# LEDBreakOutBoard.net
KiCad netlist of a schematic drawn in EAGLE
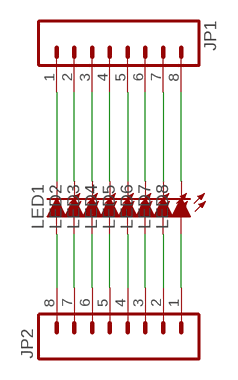
[diagram p0: schematic, sheet 1]

(export (version "E")
  (design (tool "Eeschema 10.0.6"))
  (components
    (comp (ref "JP1")
      (value "M08")
      (footprint "eagle-import:1X08")
      (libsource (lib "eagle-import") (part "M08"))
    )
    (comp (ref "JP2")
      (value "M08")
      (footprint "eagle-import:1X08")
      (libsource (lib "eagle-import") (part "M08"))
    )
    (comp (ref "LED1")
      (value "LED-0805")
      (footprint "eagle-import:LED-805")
      (libsource (lib "eagle-import") (part "LED-0805"))
    )
    (comp (ref "LED2")
      (value "LED-0805")
      (footprint "eagle-import:LED-805")
      (libsource (lib "eagle-import") (part "LED-0805"))
    )
    (comp (ref "LED3")
      (value "LED-0805")
      (footprint "eagle-import:LED-805")
      (libsource (lib "eagle-import") (part "LED-0805"))
    )
    (comp (ref "LED4")
      (value "LED-0805")
      (footprint "eagle-import:LED-805")
      (libsource (lib "eagle-import") (part "LED-0805"))
    )
    (comp (ref "LED5")
      (value "LED-0805")
      (footprint "eagle-import:LED-805")
      (libsource (lib "eagle-import") (part "LED-0805"))
    )
    (comp (ref "LED6")
      (value "LED-0805")
      (footprint "eagle-import:LED-805")
      (libsource (lib "eagle-import") (part "LED-0805"))
    )
    (comp (ref "LED7")
      (value "LED-0805")
      (footprint "eagle-import:LED-805")
      (libsource (lib "eagle-import") (part "LED-0805"))
    )
    (comp (ref "LED8")
      (value "LED-0805")
      (footprint "eagle-import:LED-805")
      (libsource (lib "eagle-import") (part "LED-0805"))
    )
  )
  (nets
    (net (code "1") (name "Net-(JP1-Pad1)") (class "Default")
      (node (ref "JP1") (pin "1") (pinfunction "1_1") (pintype "passive"))
      (node (ref "LED1") (pin "C") (pinfunction "C_C") (pintype "passive"))
    )
    (net (code "2") (name "Net-(JP1-Pad2)") (class "Default")
      (node (ref "JP1") (pin "2") (pinfunction "2_2") (pintype "passive"))
      (node (ref "LED2") (pin "C") (pinfunction "C_C") (pintype "passive"))
    )
    (net (code "3") (name "Net-(JP1-Pad3)") (class "Default")
      (node (ref "JP1") (pin "3") (pinfunction "3_3") (pintype "passive"))
      (node (ref "LED3") (pin "C") (pinfunction "C_C") (pintype "passive"))
    )
    (net (code "4") (name "Net-(JP1-Pad4)") (class "Default")
      (node (ref "JP1") (pin "4") (pinfunction "4_4") (pintype "passive"))
      (node (ref "LED4") (pin "C") (pinfunction "C_C") (pintype "passive"))
    )
    (net (code "5") (name "Net-(JP1-Pad5)") (class "Default")
      (node (ref "JP1") (pin "5") (pinfunction "5_5") (pintype "passive"))
      (node (ref "LED5") (pin "C") (pinfunction "C_C") (pintype "passive"))
    )
    (net (code "6") (name "Net-(JP1-Pad6)") (class "Default")
      (node (ref "JP1") (pin "6") (pinfunction "6_6") (pintype "passive"))
      (node (ref "LED6") (pin "C") (pinfunction "C_C") (pintype "passive"))
    )
    (net (code "7") (name "Net-(JP1-Pad7)") (class "Default")
      (node (ref "JP1") (pin "7") (pinfunction "7_7") (pintype "passive"))
      (node (ref "LED7") (pin "C") (pinfunction "C_C") (pintype "passive"))
    )
    (net (code "8") (name "Net-(JP1-Pad8)") (class "Default")
      (node (ref "JP1") (pin "8") (pinfunction "8_8") (pintype "passive"))
      (node (ref "LED8") (pin "C") (pinfunction "C_C") (pintype "passive"))
    )
    (net (code "9") (name "Net-(JP2-Pad1)") (class "Default")
      (node (ref "JP2") (pin "1") (pinfunction "1_1") (pintype "passive"))
      (node (ref "LED8") (pin "A") (pinfunction "A_A") (pintype "passive"))
    )
    (net (code "10") (name "Net-(JP2-Pad2)") (class "Default")
      (node (ref "JP2") (pin "2") (pinfunction "2_2") (pintype "passive"))
      (node (ref "LED7") (pin "A") (pinfunction "A_A") (pintype "passive"))
    )
    (net (code "11") (name "Net-(JP2-Pad3)") (class "Default")
      (node (ref "JP2") (pin "3") (pinfunction "3_3") (pintype "passive"))
      (node (ref "LED6") (pin "A") (pinfunction "A_A") (pintype "passive"))
    )
    (net (code "12") (name "Net-(JP2-Pad4)") (class "Default")
      (node (ref "JP2") (pin "4") (pinfunction "4_4") (pintype "passive"))
      (node (ref "LED5") (pin "A") (pinfunction "A_A") (pintype "passive"))
    )
    (net (code "13") (name "Net-(JP2-Pad5)") (class "Default")
      (node (ref "JP2") (pin "5") (pinfunction "5_5") (pintype "passive"))
      (node (ref "LED4") (pin "A") (pinfunction "A_A") (pintype "passive"))
    )
    (net (code "14") (name "Net-(JP2-Pad6)") (class "Default")
      (node (ref "JP2") (pin "6") (pinfunction "6_6") (pintype "passive"))
      (node (ref "LED3") (pin "A") (pinfunction "A_A") (pintype "passive"))
    )
    (net (code "15") (name "Net-(JP2-Pad7)") (class "Default")
      (node (ref "JP2") (pin "7") (pinfunction "7_7") (pintype "passive"))
      (node (ref "LED2") (pin "A") (pinfunction "A_A") (pintype "passive"))
    )
    (net (code "16") (name "Net-(JP2-Pad8)") (class "Default")
      (node (ref "JP2") (pin "8") (pinfunction "8_8") (pintype "passive"))
      (node (ref "LED1") (pin "A") (pinfunction "A_A") (pintype "passive"))
    )
  )
)
